# Sheet1.net
KiCad netlist of a schematic drawn in Altium Designer
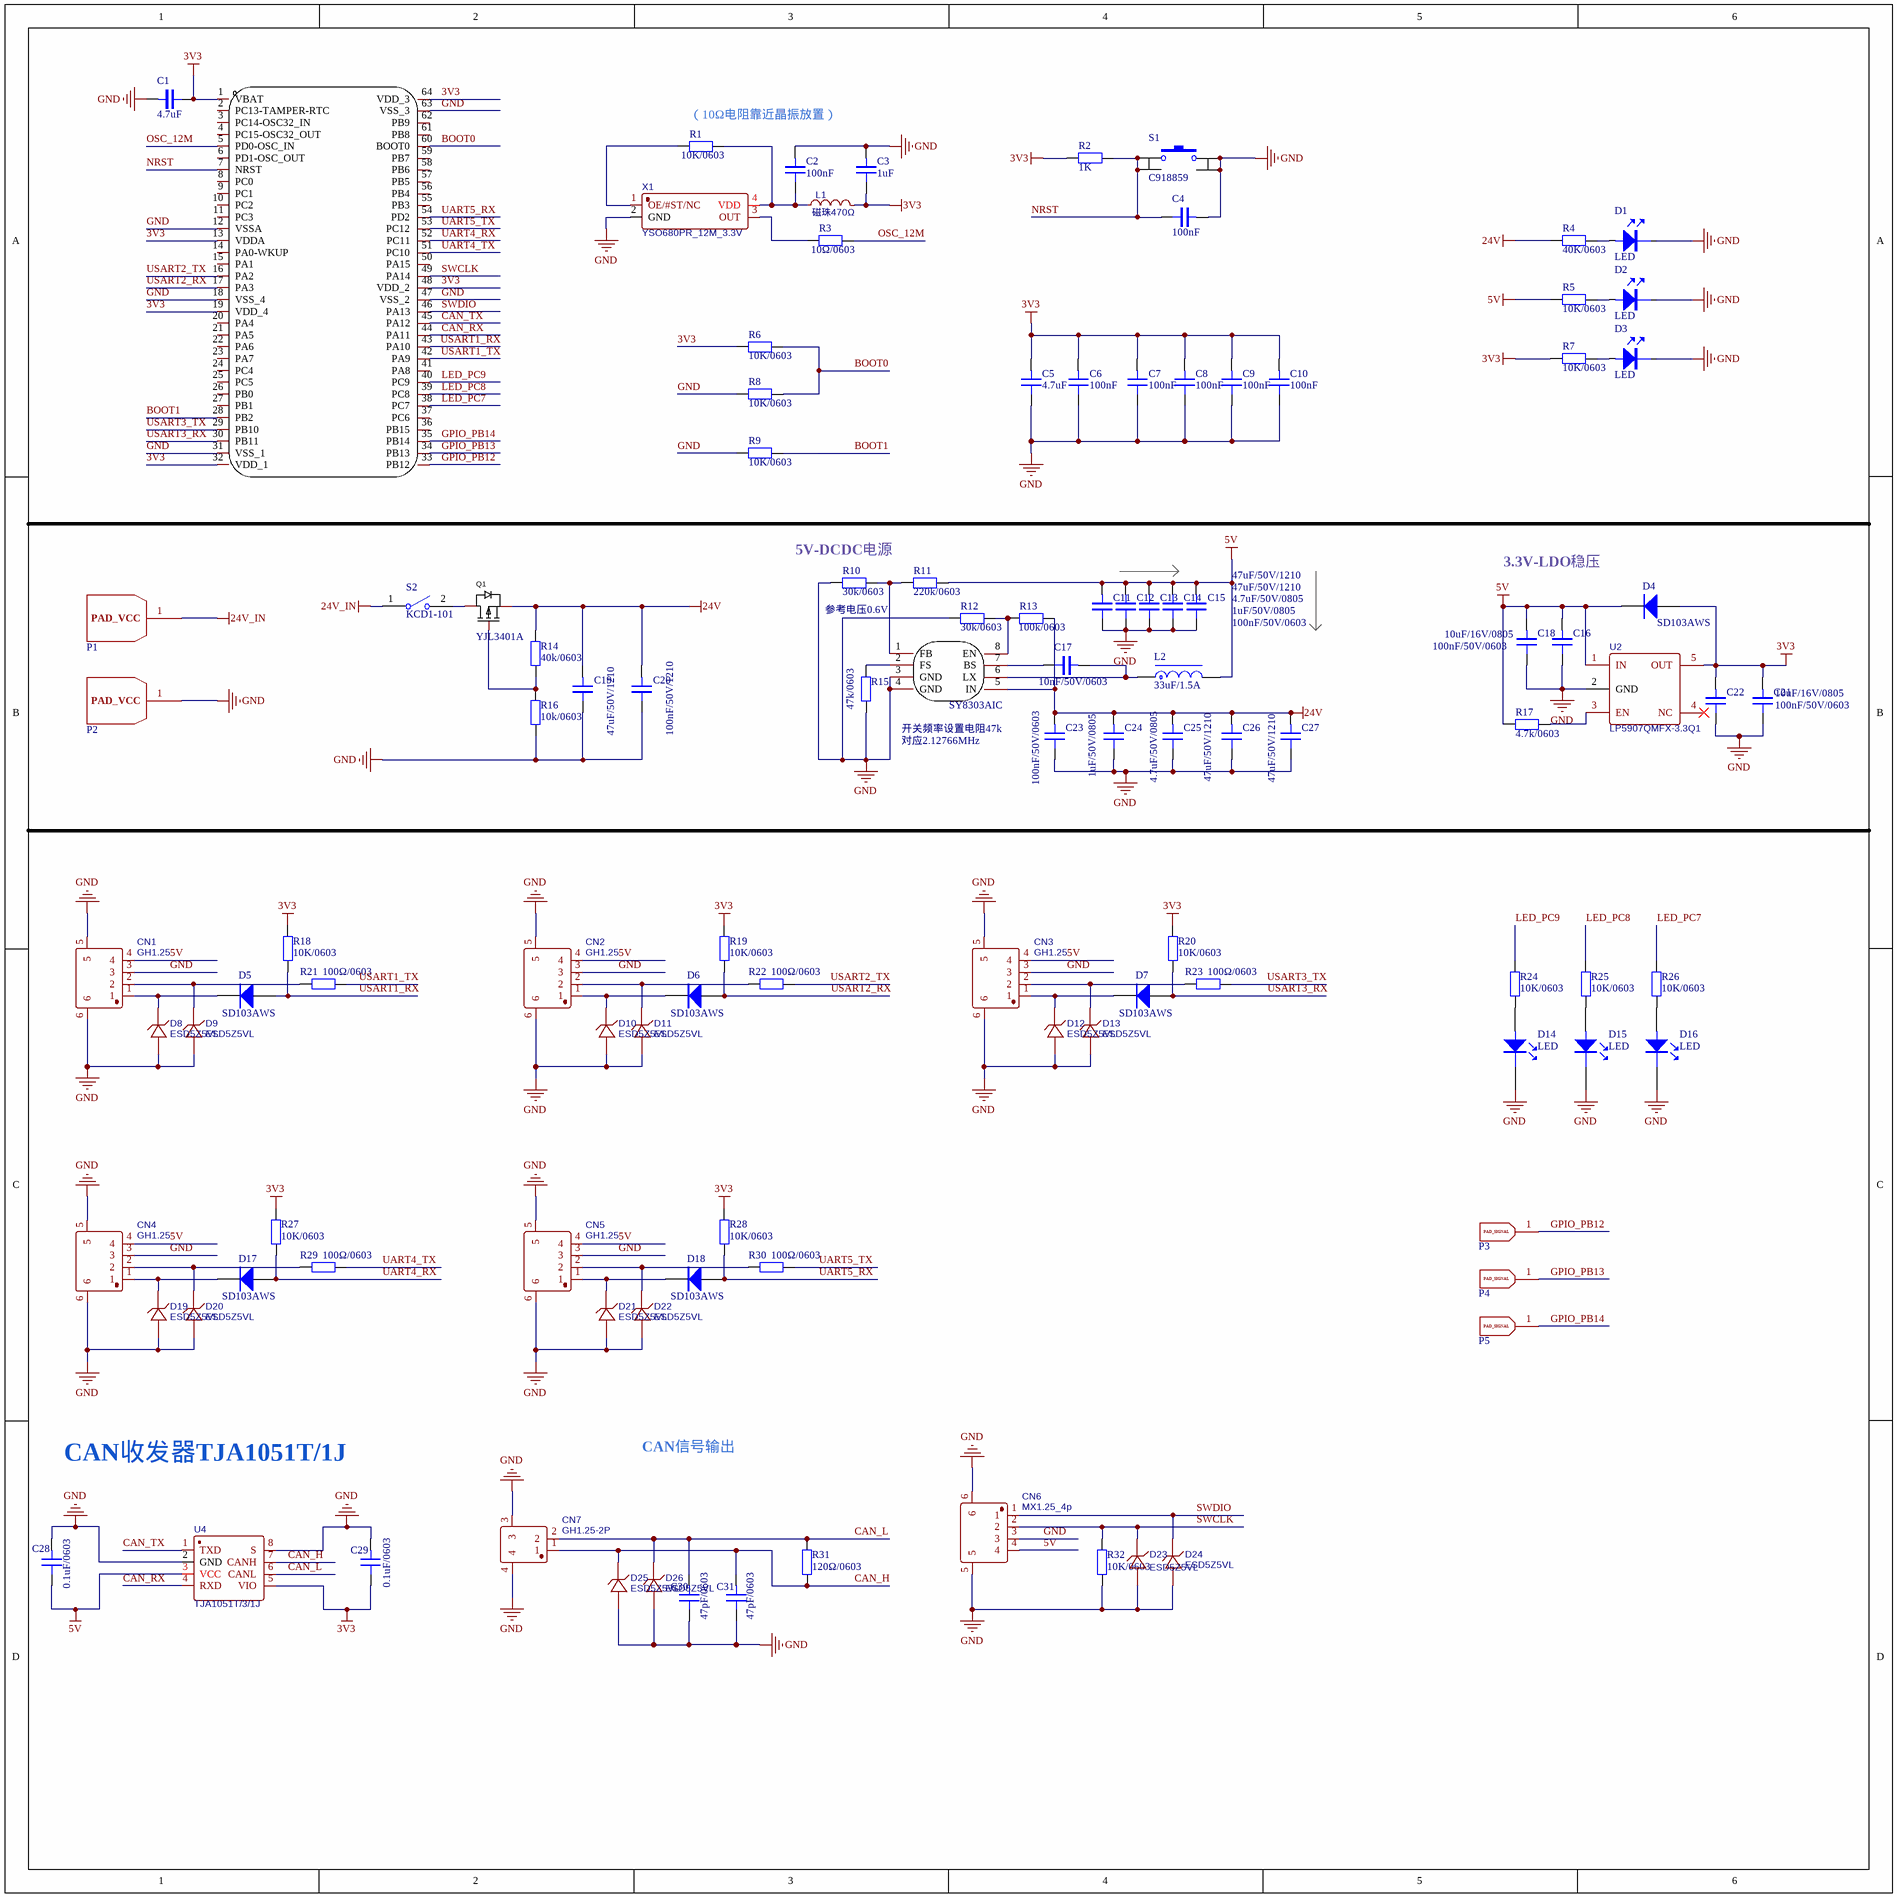
[diagram p0: Sheet1.SchDoc]

(export (version "E")
  (design (tool "Eeschema 10.0.6"))
  (components
    (comp (ref "C1")
      (value "4.7uF")
      (footprint "C 0603_L")
      (description "陶瓷电容")
      (libsource (lib "HERO_通用") (part "CAP"))
    )
    (comp (ref "C2")
      (value "100nF")
      (footprint "C 0603_L")
      (description "陶瓷电容")
      (libsource (lib "HERO_通用") (part "CAP"))
    )
    (comp (ref "C3")
      (value "1uF")
      (footprint "C 0603_L")
      (description "陶瓷电容")
      (libsource (lib "HERO_通用") (part "CAP"))
    )
    (comp (ref "C4")
      (value "100nF")
      (footprint "C 0603_L")
      (description "陶瓷电容")
      (libsource (lib "HERO_通用") (part "CAP"))
    )
    (comp (ref "C5")
      (value "4.7uF")
      (footprint "C 0603_L")
      (description "陶瓷电容")
      (libsource (lib "HERO_通用") (part "CAP"))
    )
    (comp (ref "C6")
      (value "100nF")
      (footprint "C 0603_L")
      (description "陶瓷电容")
      (libsource (lib "HERO_通用") (part "CAP"))
    )
    (comp (ref "C7")
      (value "100nF")
      (footprint "C 0603_L")
      (description "陶瓷电容")
      (libsource (lib "HERO_通用") (part "CAP"))
    )
    (comp (ref "C8")
      (value "100nF")
      (footprint "C 0603_L")
      (description "陶瓷电容")
      (libsource (lib "HERO_通用") (part "CAP"))
    )
    (comp (ref "C9")
      (value "100nF")
      (footprint "C 0603_L")
      (description "陶瓷电容")
      (libsource (lib "HERO_通用") (part "CAP"))
    )
    (comp (ref "C10")
      (value "100nF")
      (footprint "C 0603_L")
      (description "陶瓷电容")
      (libsource (lib "HERO_通用") (part "CAP"))
    )
    (comp (ref "C11")
      (value "47uF/50V/1210")
      (footprint "C 1210_L")
      (description "陶瓷电容")
      (libsource (lib "HERO_通用") (part "CAP"))
    )
    (comp (ref "C12")
      (value "47uF/50V/1210")
      (footprint "C 1210_L")
      (description "陶瓷电容")
      (libsource (lib "HERO_通用") (part "CAP"))
    )
    (comp (ref "C13")
      (value "4.7uF/50V/0805")
      (footprint "C 0805_L")
      (description "陶瓷电容")
      (libsource (lib "HERO_通用") (part "CAP"))
    )
    (comp (ref "C14")
      (value "1uF/50V/0805")
      (footprint "C 0805_L")
      (description "陶瓷电容")
      (libsource (lib "HERO_通用") (part "CAP"))
    )
    (comp (ref "C15")
      (value "100nF/50V/0603")
      (footprint "C 0603_L")
      (description "陶瓷电容")
      (libsource (lib "HERO_通用") (part "CAP"))
    )
    (comp (ref "C16")
      (value "100nF/50V/0603")
      (footprint "C 0603_L")
      (description "Capacitor")
      (libsource (lib "DJI_Armer") (part "CAP"))
    )
    (comp (ref "C17")
      (value "10nF/50V/0603")
      (footprint "C 0603_L")
      (description "陶瓷电容")
      (libsource (lib "HERO_通用") (part "CAP"))
    )
    (comp (ref "C18")
      (value "10uF/16V/0805")
      (footprint "C 0805_L")
      (description "陶瓷电容")
      (libsource (lib "HERO_通用") (part "CAP"))
    )
    (comp (ref "C19")
      (value "47uF/50V/1210")
      (footprint "C 1210_L")
      (description "陶瓷电容")
      (libsource (lib "HERO_通用") (part "CAP"))
    )
    (comp (ref "C20")
      (value "100nF/50V/1210")
      (footprint "C 0603_L")
      (description "陶瓷电容")
      (libsource (lib "HERO_通用") (part "CAP"))
    )
    (comp (ref "C21")
      (value "100nF/50V/0603")
      (footprint "C 0603_L")
      (description "Capacitor")
      (libsource (lib "DJI_Armer") (part "CAP"))
    )
    (comp (ref "C22")
      (value "10uF/16V/0805")
      (footprint "C 0805_L")
      (description "陶瓷电容")
      (libsource (lib "HERO_通用") (part "CAP"))
    )
    (comp (ref "C23")
      (value "100nF/50V/0603")
      (footprint "C 0603_L")
      (description "陶瓷电容")
      (libsource (lib "HERO_通用") (part "CAP"))
    )
    (comp (ref "C24")
      (value "1uF/50V/0805")
      (footprint "C 0805_L")
      (description "陶瓷电容")
      (libsource (lib "HERO_通用") (part "CAP"))
    )
    (comp (ref "C25")
      (value "4.7uF/50V/0805")
      (footprint "C 0805_L")
      (description "陶瓷电容")
      (libsource (lib "HERO_通用") (part "CAP"))
    )
    (comp (ref "C26")
      (value "47uF/50V/1210")
      (footprint "C 1210_L")
      (description "陶瓷电容")
      (libsource (lib "HERO_通用") (part "CAP"))
    )
    (comp (ref "C27")
      (value "47uF/50V/1210")
      (footprint "C 1210_L")
      (description "陶瓷电容")
      (libsource (lib "HERO_通用") (part "CAP"))
    )
    (comp (ref "C28")
      (value "0.1uF/0603")
      (footprint "C 0603_L")
      (description "陶瓷电容")
      (libsource (lib "HERO_通用") (part "CAP"))
    )
    (comp (ref "C29")
      (value "0.1uF/0603")
      (footprint "C 0603_L")
      (description "陶瓷电容")
      (libsource (lib "HERO_通用") (part "CAP"))
    )
    (comp (ref "C30")
      (value "47pF/0603")
      (footprint "C 0603_L")
      (description "陶瓷电容")
      (libsource (lib "HERO_通用") (part "CAP"))
    )
    (comp (ref "C31")
      (value "47pF/0603")
      (footprint "C 0603_L")
      (description "陶瓷电容")
      (libsource (lib "HERO_通用") (part "CAP"))
    )
    (comp (ref "CN1")
      (value "GH1.25")
      (footprint "GH1.25 4P-WT")
      (description "连接端子")
      (fields
        (field (name "BOM_SUPPLIER PART") "C225127")
        (field (name "BOM_MANUFACTURER PART") "A1257WR-S-4P")
        (field (name "CONTRIBUTOR") "LCSC")
      )
      (libsource (lib "HERO_交互") (part "GH1.25 4p"))
    )
    (comp (ref "CN2")
      (value "GH1.25")
      (footprint "GH1.25 4P-WT")
      (description "连接端子")
      (fields
        (field (name "BOM_SUPPLIER PART") "C225127")
        (field (name "BOM_MANUFACTURER PART") "A1257WR-S-4P")
        (field (name "CONTRIBUTOR") "LCSC")
      )
      (libsource (lib "HERO_交互") (part "GH1.25 4p"))
    )
    (comp (ref "CN3")
      (value "GH1.25")
      (footprint "GH1.25 4P-WT")
      (description "连接端子")
      (fields
        (field (name "BOM_SUPPLIER PART") "C225127")
        (field (name "BOM_MANUFACTURER PART") "A1257WR-S-4P")
        (field (name "CONTRIBUTOR") "LCSC")
      )
      (libsource (lib "HERO_交互") (part "GH1.25 4p"))
    )
    (comp (ref "CN4")
      (value "GH1.25")
      (footprint "GH1.25 4P-WT")
      (description "连接端子")
      (fields
        (field (name "BOM_SUPPLIER PART") "C225127")
        (field (name "BOM_MANUFACTURER PART") "A1257WR-S-4P")
        (field (name "CONTRIBUTOR") "LCSC")
      )
      (libsource (lib "HERO_交互") (part "GH1.25 4p"))
    )
    (comp (ref "CN5")
      (value "GH1.25")
      (footprint "GH1.25 4P-WT")
      (description "连接端子")
      (fields
        (field (name "BOM_SUPPLIER PART") "C225127")
        (field (name "BOM_MANUFACTURER PART") "A1257WR-S-4P")
        (field (name "CONTRIBUTOR") "LCSC")
      )
      (libsource (lib "HERO_交互") (part "GH1.25 4p"))
    )
    (comp (ref "CN6")
      (value "MX1.25_4p")
      (footprint "MX1.25_4PIN")
      (description "连接端子")
      (fields
        (field (name "BOM_SUPPLIER PART") "C225127")
        (field (name "BOM_MANUFACTURER PART") "A1257WR-S-4P")
        (field (name "CONTRIBUTOR") "LCSC")
      )
      (libsource (lib "HERO_交互") (part "MX1.25_4p"))
    )
    (comp (ref "CN7")
      (value "GH1.25-2P")
      (footprint "GH1.25-2P-LT")
      (description "连接端子")
      (fields
        (field (name "BOM_SUPPLIER PART") "C225125")
        (field (name "BOM_MANUFACTURER PART") "A1257WR-S-2P")
        (field (name "CONTRIBUTOR") "LCSC")
      )
      (libsource (lib "HERO_交互") (part "GH1.25-2P"))
    )
    (comp (ref "D1")
      (value "LED")
      (footprint "LED_0603")
      (description "发光二极管")
      (libsource (lib "HERO_通用") (part "LED"))
    )
    (comp (ref "D2")
      (value "LED")
      (footprint "LED_0603")
      (description "发光二极管")
      (libsource (lib "HERO_通用") (part "LED"))
    )
    (comp (ref "D3")
      (value "LED")
      (footprint "LED_0603")
      (description "发光二极管")
      (libsource (lib "HERO_通用") (part "LED"))
    )
    (comp (ref "D4")
      (value "SD103AWS")
      (footprint "SOD-323")
      (description "二极管")
      (libsource (lib "DJI_Armer") (part "SD103AWS"))
    )
    (comp (ref "D5")
      (value "SD103AWS")
      (footprint "SOD-323")
      (description "二极管")
      (libsource (lib "DJI_Armer") (part "SD103AWS"))
    )
    (comp (ref "D6")
      (value "SD103AWS")
      (footprint "SOD-323")
      (description "二极管")
      (libsource (lib "DJI_Armer") (part "SD103AWS"))
    )
    (comp (ref "D7")
      (value "SD103AWS")
      (footprint "SOD-323")
      (description "二极管")
      (libsource (lib "DJI_Armer") (part "SD103AWS"))
    )
    (comp (ref "D8")
      (value "ESD5Z5VL")
      (footprint "SOD-523")
      (description "ESD 单向 5V")
      (fields
        (field (name "BOM_MANUFACTURER PART") "SMF6.5A")
        (field (name "BOM_SUPPLIER PART") "C123792")
        (field (name "CONTRIBUTOR") "LCSC")
      )
      (libsource (lib "HERO_通用") (part "ESD5Z5VL"))
    )
    (comp (ref "D9")
      (value "ESD5Z5VL")
      (footprint "SOD-523")
      (description "ESD 单向 5V")
      (fields
        (field (name "BOM_MANUFACTURER PART") "SMF6.5A")
        (field (name "BOM_SUPPLIER PART") "C123792")
        (field (name "CONTRIBUTOR") "LCSC")
      )
      (libsource (lib "HERO_通用") (part "ESD5Z5VL"))
    )
    (comp (ref "D10")
      (value "ESD5Z5VL")
      (footprint "SOD-523")
      (description "ESD 单向 5V")
      (fields
        (field (name "BOM_MANUFACTURER PART") "SMF6.5A")
        (field (name "BOM_SUPPLIER PART") "C123792")
        (field (name "CONTRIBUTOR") "LCSC")
      )
      (libsource (lib "HERO_通用") (part "ESD5Z5VL"))
    )
    (comp (ref "D11")
      (value "ESD5Z5VL")
      (footprint "SOD-523")
      (description "ESD 单向 5V")
      (fields
        (field (name "BOM_MANUFACTURER PART") "SMF6.5A")
        (field (name "BOM_SUPPLIER PART") "C123792")
        (field (name "CONTRIBUTOR") "LCSC")
      )
      (libsource (lib "HERO_通用") (part "ESD5Z5VL"))
    )
    (comp (ref "D12")
      (value "ESD5Z5VL")
      (footprint "SOD-523")
      (description "ESD 单向 5V")
      (fields
        (field (name "BOM_MANUFACTURER PART") "SMF6.5A")
        (field (name "BOM_SUPPLIER PART") "C123792")
        (field (name "CONTRIBUTOR") "LCSC")
      )
      (libsource (lib "HERO_通用") (part "ESD5Z5VL"))
    )
    (comp (ref "D13")
      (value "ESD5Z5VL")
      (footprint "SOD-523")
      (description "ESD 单向 5V")
      (fields
        (field (name "BOM_MANUFACTURER PART") "SMF6.5A")
        (field (name "BOM_SUPPLIER PART") "C123792")
        (field (name "CONTRIBUTOR") "LCSC")
      )
      (libsource (lib "HERO_通用") (part "ESD5Z5VL"))
    )
    (comp (ref "D14")
      (value "LED")
      (footprint "LED_0603")
      (description "发光二极管")
      (libsource (lib "") (part "LED_1"))
    )
    (comp (ref "D15")
      (value "LED")
      (footprint "LED_0603")
      (description "发光二极管")
      (libsource (lib "") (part "LED_1"))
    )
    (comp (ref "D16")
      (value "LED")
      (footprint "LED_0603")
      (description "发光二极管")
      (libsource (lib "") (part "LED_1"))
    )
    (comp (ref "D17")
      (value "SD103AWS")
      (footprint "SOD-323")
      (description "二极管")
      (libsource (lib "DJI_Armer") (part "SD103AWS"))
    )
    (comp (ref "D18")
      (value "SD103AWS")
      (footprint "SOD-323")
      (description "二极管")
      (libsource (lib "DJI_Armer") (part "SD103AWS"))
    )
    (comp (ref "D19")
      (value "ESD5Z5VL")
      (footprint "SOD-523")
      (description "ESD 单向 5V")
      (fields
        (field (name "BOM_MANUFACTURER PART") "SMF6.5A")
        (field (name "BOM_SUPPLIER PART") "C123792")
        (field (name "CONTRIBUTOR") "LCSC")
      )
      (libsource (lib "HERO_通用") (part "ESD5Z5VL"))
    )
    (comp (ref "D20")
      (value "ESD5Z5VL")
      (footprint "SOD-523")
      (description "ESD 单向 5V")
      (fields
        (field (name "BOM_MANUFACTURER PART") "SMF6.5A")
        (field (name "BOM_SUPPLIER PART") "C123792")
        (field (name "CONTRIBUTOR") "LCSC")
      )
      (libsource (lib "HERO_通用") (part "ESD5Z5VL"))
    )
    (comp (ref "D21")
      (value "ESD5Z5VL")
      (footprint "SOD-523")
      (description "ESD 单向 5V")
      (fields
        (field (name "BOM_MANUFACTURER PART") "SMF6.5A")
        (field (name "BOM_SUPPLIER PART") "C123792")
        (field (name "CONTRIBUTOR") "LCSC")
      )
      (libsource (lib "HERO_通用") (part "ESD5Z5VL"))
    )
    (comp (ref "D22")
      (value "ESD5Z5VL")
      (footprint "SOD-523")
      (description "ESD 单向 5V")
      (fields
        (field (name "BOM_MANUFACTURER PART") "SMF6.5A")
        (field (name "BOM_SUPPLIER PART") "C123792")
        (field (name "CONTRIBUTOR") "LCSC")
      )
      (libsource (lib "HERO_通用") (part "ESD5Z5VL"))
    )
    (comp (ref "D23")
      (value "ESD5Z5VL")
      (footprint "SOD-523")
      (description "ESD 单向 5V")
      (fields
        (field (name "BOM_MANUFACTURER PART") "SMF6.5A")
        (field (name "BOM_SUPPLIER PART") "C123792")
        (field (name "CONTRIBUTOR") "LCSC")
      )
      (libsource (lib "HERO_通用") (part "ESD5Z5VL"))
    )
    (comp (ref "D24")
      (value "ESD5Z5VL")
      (footprint "SOD-523")
      (description "ESD 单向 5V")
      (fields
        (field (name "BOM_MANUFACTURER PART") "SMF6.5A")
        (field (name "BOM_SUPPLIER PART") "C123792")
        (field (name "CONTRIBUTOR") "LCSC")
      )
      (libsource (lib "HERO_通用") (part "ESD5Z5VL"))
    )
    (comp (ref "D25")
      (value "ESD5Z5VL")
      (footprint "SOD-523")
      (description "ESD 单向 5V")
      (fields
        (field (name "BOM_MANUFACTURER PART") "SMF6.5A")
        (field (name "BOM_SUPPLIER PART") "C123792")
        (field (name "CONTRIBUTOR") "LCSC")
      )
      (libsource (lib "HERO_通用") (part "ESD5Z5VL"))
    )
    (comp (ref "D26")
      (value "ESD5Z5VL")
      (footprint "SOD-523")
      (description "ESD 单向 5V")
      (fields
        (field (name "BOM_MANUFACTURER PART") "SMF6.5A")
        (field (name "BOM_SUPPLIER PART") "C123792")
        (field (name "CONTRIBUTOR") "LCSC")
      )
      (libsource (lib "HERO_通用") (part "ESD5Z5VL"))
    )
    (comp (ref "L1")
      (value "磁珠470Ω")
      (footprint "C 0603_L")
      (fields
        (field (name "BOM_MANUFACTURER PART") "UPZ1608U471-1R5TF")
        (field (name "BOM_SUPPLIER PART") "C74335")
      )
      (libsource (lib "HERO_通用") (part "磁珠470Ω"))
    )
    (comp (ref "L2")
      (value "33uF/1.5A")
      (footprint "IND-SMD_L7.3-W7.3")
      (description "贴片功率电感")
      (libsource (lib "Schlib1") (part "L-SMD"))
    )
    (comp (ref "P1") (value "PAD_VCC") (footprint "PAD_VCC") (libsource (lib "HERO_模块") (part "PAD_VCC")))
    (comp (ref "P2") (value "PAD_VCC") (footprint "PAD_VCC") (libsource (lib "HERO_模块") (part "PAD_VCC")))
    (comp (ref "P3")
      (value "PAD_Signal")
      (footprint "pad_signal")
      (libsource (lib "HERO_模块") (part "PAD_Signal"))
    )
    (comp (ref "P4")
      (value "PAD_Signal")
      (footprint "pad_signal")
      (libsource (lib "HERO_模块") (part "PAD_Signal"))
    )
    (comp (ref "P5")
      (value "PAD_Signal")
      (footprint "pad_signal")
      (libsource (lib "HERO_模块") (part "PAD_Signal"))
    )
    (comp (ref "Q1")
      (value "YJL3401A")
      (footprint "SOT-23-3_L2.9-W1.3-P1.90-LS2.4-BR")
      (fields (field (name "MANUFACTURER") "YANGJIE(扬杰)"))
      (libsource (lib "EG_slave_STCG12") (part "YJL3401A"))
    )
    (comp (ref "R1")
      (value "10K/0603")
      (footprint "R 0603_S")
      (description "贴片电阻")
      (libsource (lib "HERO_通用") (part "RES"))
    )
    (comp (ref "R2")
      (value "1K")
      (footprint "R 0603_S")
      (description "贴片电阻")
      (libsource (lib "HERO_通用") (part "RES"))
    )
    (comp (ref "R3")
      (value "10Ω/0603")
      (footprint "R 0603_S")
      (description "贴片电阻")
      (libsource (lib "HERO_通用") (part "RES"))
    )
    (comp (ref "R4")
      (value "40K/0603")
      (footprint "R 0603_S")
      (description "贴片电阻")
      (libsource (lib "HERO_通用") (part "RES"))
    )
    (comp (ref "R5")
      (value "10K/0603")
      (footprint "R 0603_S")
      (description "贴片电阻")
      (libsource (lib "HERO_通用") (part "RES"))
    )
    (comp (ref "R6")
      (value "10K/0603")
      (footprint "R 0603_S")
      (description "贴片电阻")
      (libsource (lib "HERO_通用") (part "RES"))
    )
    (comp (ref "R7")
      (value "10K/0603")
      (footprint "R 0603_S")
      (description "贴片电阻")
      (libsource (lib "HERO_通用") (part "RES"))
    )
    (comp (ref "R8")
      (value "10K/0603")
      (footprint "R 0603_S")
      (description "贴片电阻")
      (libsource (lib "HERO_通用") (part "RES"))
    )
    (comp (ref "R9")
      (value "10K/0603")
      (footprint "R 0603_S")
      (description "贴片电阻")
      (libsource (lib "HERO_通用") (part "RES"))
    )
    (comp (ref "R10")
      (value "30k/0603")
      (footprint "R 0603_S")
      (description "贴片电阻")
      (libsource (lib "HERO_通用") (part "RES"))
    )
    (comp (ref "R11")
      (value "220k/0603")
      (footprint "R 0603_S")
      (description "贴片电阻")
      (libsource (lib "HERO_通用") (part "RES"))
    )
    (comp (ref "R12")
      (value "30k/0603")
      (footprint "R 0603_S")
      (description "贴片电阻")
      (libsource (lib "HERO_通用") (part "RES"))
    )
    (comp (ref "R13")
      (value "100k/0603")
      (footprint "R 0603_S")
      (description "贴片电阻")
      (libsource (lib "HERO_通用") (part "RES"))
    )
    (comp (ref "R14")
      (value "40k/0603")
      (footprint "R 0603_S")
      (description "贴片电阻")
      (libsource (lib "") (part "RES_1"))
    )
    (comp (ref "R15")
      (value "47k/0603")
      (footprint "R 0603_S")
      (description "贴片电阻")
      (libsource (lib "") (part "RES_1"))
    )
    (comp (ref "R16")
      (value "10k/0603")
      (footprint "R 0603_S")
      (description "贴片电阻")
      (libsource (lib "") (part "RES_1"))
    )
    (comp (ref "R17")
      (value "4.7k/0603")
      (footprint "R 0603_S")
      (description "贴片电阻")
      (libsource (lib "HERO_通用") (part "RES"))
    )
    (comp (ref "R18")
      (value "10K/0603")
      (footprint "R 0603_S")
      (description "贴片电阻")
      (libsource (lib "") (part "RES_1"))
    )
    (comp (ref "R19")
      (value "10K/0603")
      (footprint "R 0603_S")
      (description "贴片电阻")
      (libsource (lib "") (part "RES_1"))
    )
    (comp (ref "R20")
      (value "10K/0603")
      (footprint "R 0603_S")
      (description "贴片电阻")
      (libsource (lib "") (part "RES_1"))
    )
    (comp (ref "R21")
      (value "100Ω/0603")
      (footprint "R 0603_S")
      (description "贴片电阻")
      (libsource (lib "HERO_通用") (part "RES"))
    )
    (comp (ref "R22")
      (value "100Ω/0603")
      (footprint "R 0603_S")
      (description "贴片电阻")
      (libsource (lib "HERO_通用") (part "RES"))
    )
    (comp (ref "R23")
      (value "100Ω/0603")
      (footprint "R 0603_S")
      (description "贴片电阻")
      (libsource (lib "HERO_通用") (part "RES"))
    )
    (comp (ref "R24")
      (value "10K/0603")
      (footprint "R 0603_S")
      (description "贴片电阻")
      (libsource (lib "") (part "RES_1"))
    )
    (comp (ref "R25")
      (value "10K/0603")
      (footprint "R 0603_S")
      (description "贴片电阻")
      (libsource (lib "") (part "RES_1"))
    )
    (comp (ref "R26")
      (value "10K/0603")
      (footprint "R 0603_S")
      (description "贴片电阻")
      (libsource (lib "") (part "RES_1"))
    )
    (comp (ref "R27")
      (value "10K/0603")
      (footprint "R 0603_S")
      (description "贴片电阻")
      (libsource (lib "") (part "RES_1"))
    )
    (comp (ref "R28")
      (value "10K/0603")
      (footprint "R 0603_S")
      (description "贴片电阻")
      (libsource (lib "") (part "RES_1"))
    )
    (comp (ref "R29")
      (value "100Ω/0603")
      (footprint "R 0603_S")
      (description "贴片电阻")
      (libsource (lib "HERO_通用") (part "RES"))
    )
    (comp (ref "R30")
      (value "100Ω/0603")
      (footprint "R 0603_S")
      (description "贴片电阻")
      (libsource (lib "HERO_通用") (part "RES"))
    )
    (comp (ref "R31")
      (value "120Ω/0603")
      (footprint "R 0603_S")
      (description "贴片电阻")
      (libsource (lib "") (part "RES_1"))
    )
    (comp (ref "R32")
      (value "10K/0603")
      (footprint "R 0603_S")
      (description "贴片电阻")
      (libsource (lib "") (part "RES_1"))
    )
    (comp (ref "S1")
      (value "C918859")
      (footprint "KEY-4.2*3.25")
      (description "DJI御用小按键")
      (libsource (lib "HERO_交互") (part "按键"))
    )
    (comp (ref "S2")
      (value "KCD1-101")
      (footprint "SW-TH_MR5-111-C5N-BB")
      (description "单刀单掷 直插立式")
      (libsource (lib "HERO_交互") (part "KCD1-101"))
    )
    (comp (ref "U1")
      (value "STM32F103RCT6")
      (footprint "LQFP-64_L10.0-W10.0-P0.50-LS12.0-BL")
      (fields (field (name "MANUFACTURER") "ST(意法半导体)"))
      (libsource (lib "Schlib1") (part "STM32F103RCT6"))
    )
    (comp (ref "U2")
      (value "LP5907QMFX-3.3Q1")
      (footprint "SOT23-5N")
      (fields (field (name "BOM_SUPPLIER PART") "C130005") (field (name "CONTRIBUTOR") "LCSC"))
      (libsource (lib "DJI_Armer") (part "LP5907QMFX-3.3Q1"))
    )
    (comp (ref "U3")
      (value "SY8303AIC")
      (footprint "TSOT-23-8_L2.9-W1.6-P0.65-LS2.8-BR")
      (description "DCDC ADJ 3A")
      (fields (field (name "MANUFACTURER") "矽力杰silergy"))
      (libsource (lib "HERO_IC") (part "SY8303AIC"))
    )
    (comp (ref "U4")
      (value "TJA1051T/3/1J")
      (footprint "SOP8_L")
      (description "CAN芯片")
      (fields (field (name "BOM_SUPPLIER PART") "C38695"))
      (libsource (lib "HERO_IC") (part "TJA1051T/3/1J"))
    )
    (comp (ref "X1")
      (value "YSO680PR_12M_3.3V")
      (footprint "OSC 3225-4P")
      (description "有源晶振12M")
      (fields
        (field (name "BOM_SUPPLIER PART") "C382483")
        (field (name "BOM_MANUFACTURER PART") "OP322512MEDA4SI-u")
        (field (name "CONTRIBUTOR") "LCSC")
      )
      (libsource (lib "HERO_IC") (part "YSO680PR_12M_3.3V"))
    )
  )
  (nets
    (net (code "1") (name "/BOOT0") (class "Default")
      (node (ref "R6") (pin "2") (pinfunction "2_2") (pintype "passive"))
      (node (ref "R8") (pin "2") (pinfunction "2_2") (pintype "passive"))
      (node (ref "U1") (pin "60") (pinfunction "BOOT0_60") (pintype "passive"))
    )
    (net (code "2") (name "/BOOT1") (class "Default")
      (node (ref "R9") (pin "2") (pinfunction "2_2") (pintype "passive"))
      (node (ref "U1") (pin "28") (pinfunction "PB2_28") (pintype "passive"))
    )
    (net (code "3") (name "/CAN_H") (class "Default")
      (node (ref "C31") (pin "1") (pinfunction "1_1") (pintype "passive"))
      (node (ref "CN7") (pin "1") (pinfunction "1_1") (pintype "passive"))
      (node (ref "D25") (pin "2") (pinfunction "C_2") (pintype "passive"))
      (node (ref "R31") (pin "2") (pinfunction "2_2") (pintype "passive"))
      (node (ref "U4") (pin "7") (pinfunction "CANH_7") (pintype "passive"))
    )
    (net (code "4") (name "/CAN_L") (class "Default")
      (node (ref "C30") (pin "1") (pinfunction "1_1") (pintype "passive"))
      (node (ref "CN7") (pin "2") (pinfunction "2_2") (pintype "passive"))
      (node (ref "D26") (pin "2") (pinfunction "C_2") (pintype "passive"))
      (node (ref "R31") (pin "1") (pinfunction "1_1") (pintype "passive"))
      (node (ref "U4") (pin "6") (pinfunction "CANL_6") (pintype "passive"))
    )
    (net (code "5") (name "/CAN_RX") (class "Default")
      (node (ref "U1") (pin "44") (pinfunction "PA11_44") (pintype "passive"))
      (node (ref "U4") (pin "4") (pinfunction "RXD_4") (pintype "passive"))
    )
    (net (code "6") (name "/CAN_TX") (class "Default")
      (node (ref "U1") (pin "45") (pinfunction "PA12_45") (pintype "passive"))
      (node (ref "U4") (pin "1") (pinfunction "TXD_1") (pintype "passive"))
    )
    (net (code "7") (name "/GPIO_PB12") (class "Default")
      (node (ref "P3") (pin "1") (pinfunction "PAD_SIGNAL_1") (pintype "passive"))
      (node (ref "U1") (pin "33") (pinfunction "PB12_33") (pintype "passive"))
    )
    (net (code "8") (name "/GPIO_PB13") (class "Default")
      (node (ref "P4") (pin "1") (pinfunction "PAD_SIGNAL_1") (pintype "passive"))
      (node (ref "U1") (pin "34") (pinfunction "PB13_34") (pintype "passive"))
    )
    (net (code "9") (name "/GPIO_PB14") (class "Default")
      (node (ref "P5") (pin "1") (pinfunction "PAD_SIGNAL_1") (pintype "passive"))
      (node (ref "U1") (pin "35") (pinfunction "PB14_35") (pintype "passive"))
    )
    (net (code "10") (name "/LED_PC7") (class "Default")
      (node (ref "R26") (pin "1") (pinfunction "1_1") (pintype "passive"))
      (node (ref "U1") (pin "38") (pinfunction "PC7_38") (pintype "passive"))
    )
    (net (code "11") (name "/LED_PC8") (class "Default")
      (node (ref "R25") (pin "1") (pinfunction "1_1") (pintype "passive"))
      (node (ref "U1") (pin "39") (pinfunction "PC8_39") (pintype "passive"))
    )
    (net (code "12") (name "/LED_PC9") (class "Default")
      (node (ref "R24") (pin "1") (pinfunction "1_1") (pintype "passive"))
      (node (ref "U1") (pin "40") (pinfunction "PC9_40") (pintype "passive"))
    )
    (net (code "13") (name "/NRST") (class "Default")
      (node (ref "C4") (pin "2") (pinfunction "2_2") (pintype "passive"))
      (node (ref "R2") (pin "2") (pinfunction "2_2") (pintype "passive"))
      (node (ref "S1") (pin "1") (pinfunction "1_1") (pintype "passive"))
      (node (ref "S1") (pin "2") (pinfunction "2_2") (pintype "passive"))
      (node (ref "U1") (pin "7") (pinfunction "NRST_7") (pintype "passive"))
    )
    (net (code "14") (name "/OSC_12M") (class "Default")
      (node (ref "R3") (pin "2") (pinfunction "2_2") (pintype "passive"))
      (node (ref "U1") (pin "5") (pinfunction "PD0-OSC_IN_5") (pintype "passive"))
    )
    (net (code "15") (name "/SWCLK") (class "Default")
      (node (ref "CN6") (pin "2") (pinfunction "2_2") (pintype "passive"))
      (node (ref "D23") (pin "2") (pinfunction "C_2") (pintype "passive"))
      (node (ref "R32") (pin "1") (pinfunction "1_1") (pintype "passive"))
      (node (ref "U1") (pin "49") (pinfunction "PA14_49") (pintype "passive"))
    )
    (net (code "16") (name "/SWDIO") (class "Default")
      (node (ref "CN6") (pin "1") (pinfunction "1_1") (pintype "passive"))
      (node (ref "D24") (pin "2") (pinfunction "C_2") (pintype "passive"))
      (node (ref "U1") (pin "46") (pinfunction "PA13_46") (pintype "passive"))
    )
    (net (code "17") (name "/UART4_RX") (class "Default")
      (node (ref "D17") (pin "1") (pinfunction "1_1") (pintype "passive"))
      (node (ref "R27") (pin "2") (pinfunction "2_2") (pintype "passive"))
      (node (ref "U1") (pin "52") (pinfunction "PC11_52") (pintype "passive"))
    )
    (net (code "18") (name "/UART4_TX") (class "Default")
      (node (ref "R29") (pin "2") (pinfunction "2_2") (pintype "passive"))
      (node (ref "U1") (pin "51") (pinfunction "PC10_51") (pintype "passive"))
    )
    (net (code "19") (name "/UART5_RX") (class "Default")
      (node (ref "D18") (pin "1") (pinfunction "1_1") (pintype "passive"))
      (node (ref "R28") (pin "2") (pinfunction "2_2") (pintype "passive"))
      (node (ref "U1") (pin "54") (pinfunction "PD2_54") (pintype "passive"))
    )
    (net (code "20") (name "/UART5_TX") (class "Default")
      (node (ref "R30") (pin "2") (pinfunction "2_2") (pintype "passive"))
      (node (ref "U1") (pin "53") (pinfunction "PC12_53") (pintype "passive"))
    )
    (net (code "21") (name "/USART1_RX") (class "Default")
      (node (ref "D5") (pin "1") (pinfunction "1_1") (pintype "passive"))
      (node (ref "R18") (pin "2") (pinfunction "2_2") (pintype "passive"))
      (node (ref "U1") (pin "43") (pinfunction "PA10_43") (pintype "passive"))
    )
    (net (code "22") (name "/USART1_TX") (class "Default")
      (node (ref "R21") (pin "2") (pinfunction "2_2") (pintype "passive"))
      (node (ref "U1") (pin "42") (pinfunction "PA9_42") (pintype "passive"))
    )
    (net (code "23") (name "/USART2_RX") (class "Default")
      (node (ref "D6") (pin "1") (pinfunction "1_1") (pintype "passive"))
      (node (ref "R19") (pin "2") (pinfunction "2_2") (pintype "passive"))
      (node (ref "U1") (pin "17") (pinfunction "PA3_17") (pintype "passive"))
    )
    (net (code "24") (name "/USART2_TX") (class "Default")
      (node (ref "R22") (pin "2") (pinfunction "2_2") (pintype "passive"))
      (node (ref "U1") (pin "16") (pinfunction "PA2_16") (pintype "passive"))
    )
    (net (code "25") (name "/USART3_RX") (class "Default")
      (node (ref "D7") (pin "1") (pinfunction "1_1") (pintype "passive"))
      (node (ref "R20") (pin "2") (pinfunction "2_2") (pintype "passive"))
      (node (ref "U1") (pin "30") (pinfunction "PB11_30") (pintype "passive"))
    )
    (net (code "26") (name "/USART3_TX") (class "Default")
      (node (ref "R23") (pin "2") (pinfunction "2_2") (pintype "passive"))
      (node (ref "U1") (pin "29") (pinfunction "PB10_29") (pintype "passive"))
    )
    (net (code "27") (name "3V3") (class "Default")
      (node (ref "C1") (pin "2") (pinfunction "2_2") (pintype "passive"))
      (node (ref "C10") (pin "1") (pinfunction "1_1") (pintype "passive"))
      (node (ref "C21") (pin "1") (pinfunction "1_1") (pintype "passive"))
      (node (ref "C22") (pin "1") (pinfunction "1_1") (pintype "passive"))
      (node (ref "C29") (pin "2") (pinfunction "2_2") (pintype "passive"))
      (node (ref "C3") (pin "2") (pinfunction "2_2") (pintype "passive"))
      (node (ref "C5") (pin "1") (pinfunction "1_1") (pintype "passive"))
      (node (ref "C6") (pin "1") (pinfunction "1_1") (pintype "passive"))
      (node (ref "C7") (pin "1") (pinfunction "1_1") (pintype "passive"))
      (node (ref "C8") (pin "1") (pinfunction "1_1") (pintype "passive"))
      (node (ref "C9") (pin "1") (pinfunction "1_1") (pintype "passive"))
      (node (ref "D4") (pin "1") (pinfunction "1_1") (pintype "passive"))
      (node (ref "L1") (pin "2") (pinfunction "2_2") (pintype "passive"))
      (node (ref "R18") (pin "1") (pinfunction "1_1") (pintype "passive"))
      (node (ref "R19") (pin "1") (pinfunction "1_1") (pintype "passive"))
      (node (ref "R2") (pin "1") (pinfunction "1_1") (pintype "passive"))
      (node (ref "R20") (pin "1") (pinfunction "1_1") (pintype "passive"))
      (node (ref "R27") (pin "1") (pinfunction "1_1") (pintype "passive"))
      (node (ref "R28") (pin "1") (pinfunction "1_1") (pintype "passive"))
      (node (ref "R6") (pin "1") (pinfunction "1_1") (pintype "passive"))
      (node (ref "R7") (pin "1") (pinfunction "1_1") (pintype "passive"))
      (node (ref "U1") (pin "1") (pinfunction "VBAT_1") (pintype "passive"))
      (node (ref "U1") (pin "13") (pinfunction "VDDA_13") (pintype "passive"))
      (node (ref "U1") (pin "19") (pinfunction "VDD_4_19") (pintype "passive"))
      (node (ref "U1") (pin "32") (pinfunction "VDD_1_32") (pintype "passive"))
      (node (ref "U1") (pin "48") (pinfunction "VDD_2_48") (pintype "passive"))
      (node (ref "U1") (pin "64") (pinfunction "VDD_3_64") (pintype "passive"))
      (node (ref "U2") (pin "5") (pinfunction "OUT_5") (pintype "passive"))
      (node (ref "U4") (pin "5") (pinfunction "VIO_5") (pintype "passive"))
    )
    (net (code "28") (name "5V") (class "Default")
      (node (ref "C11") (pin "1") (pinfunction "1_1") (pintype "passive"))
      (node (ref "C12") (pin "1") (pinfunction "1_1") (pintype "passive"))
      (node (ref "C13") (pin "1") (pinfunction "1_1") (pintype "passive"))
      (node (ref "C14") (pin "1") (pinfunction "1_1") (pintype "passive"))
      (node (ref "C15") (pin "1") (pinfunction "1_1") (pintype "passive"))
      (node (ref "C16") (pin "1") (pinfunction "1_1") (pintype "passive"))
      (node (ref "C18") (pin "1") (pinfunction "1_1") (pintype "passive"))
      (node (ref "C28") (pin "2") (pinfunction "2_2") (pintype "passive"))
      (node (ref "CN1") (pin "4") (pinfunction "4_4") (pintype "passive"))
      (node (ref "CN2") (pin "4") (pinfunction "4_4") (pintype "passive"))
      (node (ref "CN3") (pin "4") (pinfunction "4_4") (pintype "passive"))
      (node (ref "CN4") (pin "4") (pinfunction "4_4") (pintype "passive"))
      (node (ref "CN5") (pin "4") (pinfunction "4_4") (pintype "passive"))
      (node (ref "CN6") (pin "4") (pinfunction "4_4") (pintype "passive"))
      (node (ref "D4") (pin "2") (pinfunction "2_2") (pintype "passive"))
      (node (ref "L2") (pin "2") (pinfunction "2_2") (pintype "passive"))
      (node (ref "R11") (pin "2") (pinfunction "2_2") (pintype "passive"))
      (node (ref "R17") (pin "1") (pinfunction "1_1") (pintype "passive"))
      (node (ref "R5") (pin "1") (pinfunction "1_1") (pintype "passive"))
      (node (ref "U2") (pin "1") (pinfunction "IN_1") (pintype "passive"))
      (node (ref "U4") (pin "3") (pinfunction "VCC_3") (pintype "passive"))
    )
    (net (code "29") (name "24V") (class "Default")
      (node (ref "C19") (pin "1") (pinfunction "1_1") (pintype "passive"))
      (node (ref "C20") (pin "1") (pinfunction "1_1") (pintype "passive"))
      (node (ref "C23") (pin "1") (pinfunction "1_1") (pintype "passive"))
      (node (ref "C24") (pin "1") (pinfunction "1_1") (pintype "passive"))
      (node (ref "C25") (pin "1") (pinfunction "1_1") (pintype "passive"))
      (node (ref "C26") (pin "1") (pinfunction "1_1") (pintype "passive"))
      (node (ref "C27") (pin "1") (pinfunction "1_1") (pintype "passive"))
      (node (ref "Q1") (pin "2") (pinfunction "S_2") (pintype "passive"))
      (node (ref "R13") (pin "2") (pinfunction "2_2") (pintype "passive"))
      (node (ref "R14") (pin "1") (pinfunction "1_1") (pintype "passive"))
      (node (ref "R4") (pin "1") (pinfunction "1_1") (pintype "passive"))
      (node (ref "U3") (pin "5") (pinfunction "IN_5") (pintype "passive"))
    )
    (net (code "30") (name "24V_IN") (class "Default")
      (node (ref "P1") (pin "1") (pinfunction "PAD_VCC_1") (pintype "passive"))
      (node (ref "S2") (pin "1") (pinfunction "1_1") (pintype "passive"))
    )
    (net (code "31") (name "GND") (class "Default")
      (node (ref "C1") (pin "1") (pinfunction "1_1") (pintype "passive"))
      (node (ref "C10") (pin "2") (pinfunction "2_2") (pintype "passive"))
      (node (ref "C11") (pin "2") (pinfunction "2_2") (pintype "passive"))
      (node (ref "C12") (pin "2") (pinfunction "2_2") (pintype "passive"))
      (node (ref "C13") (pin "2") (pinfunction "2_2") (pintype "passive"))
      (node (ref "C14") (pin "2") (pinfunction "2_2") (pintype "passive"))
      (node (ref "C15") (pin "2") (pinfunction "2_2") (pintype "passive"))
      (node (ref "C16") (pin "2") (pinfunction "2_2") (pintype "passive"))
      (node (ref "C18") (pin "2") (pinfunction "2_2") (pintype "passive"))
      (node (ref "C19") (pin "2") (pinfunction "2_2") (pintype "passive"))
      (node (ref "C2") (pin "1") (pinfunction "1_1") (pintype "passive"))
      (node (ref "C20") (pin "2") (pinfunction "2_2") (pintype "passive"))
      (node (ref "C21") (pin "2") (pinfunction "2_2") (pintype "passive"))
      (node (ref "C22") (pin "2") (pinfunction "2_2") (pintype "passive"))
      (node (ref "C23") (pin "2") (pinfunction "2_2") (pintype "passive"))
      (node (ref "C24") (pin "2") (pinfunction "2_2") (pintype "passive"))
      (node (ref "C25") (pin "2") (pinfunction "2_2") (pintype "passive"))
      (node (ref "C26") (pin "2") (pinfunction "2_2") (pintype "passive"))
      (node (ref "C27") (pin "2") (pinfunction "2_2") (pintype "passive"))
      (node (ref "C28") (pin "1") (pinfunction "1_1") (pintype "passive"))
      (node (ref "C29") (pin "1") (pinfunction "1_1") (pintype "passive"))
      (node (ref "C3") (pin "1") (pinfunction "1_1") (pintype "passive"))
      (node (ref "C30") (pin "2") (pinfunction "2_2") (pintype "passive"))
      (node (ref "C31") (pin "2") (pinfunction "2_2") (pintype "passive"))
      (node (ref "C4") (pin "1") (pinfunction "1_1") (pintype "passive"))
      (node (ref "C5") (pin "2") (pinfunction "2_2") (pintype "passive"))
      (node (ref "C6") (pin "2") (pinfunction "2_2") (pintype "passive"))
      (node (ref "C7") (pin "2") (pinfunction "2_2") (pintype "passive"))
      (node (ref "C8") (pin "2") (pinfunction "2_2") (pintype "passive"))
      (node (ref "C9") (pin "2") (pinfunction "2_2") (pintype "passive"))
      (node (ref "CN1") (pin "3") (pinfunction "3_3") (pintype "passive"))
      (node (ref "CN1") (pin "5") (pinfunction "5_5") (pintype "passive"))
      (node (ref "CN1") (pin "6") (pinfunction "6_6") (pintype "passive"))
      (node (ref "CN2") (pin "3") (pinfunction "3_3") (pintype "passive"))
      (node (ref "CN2") (pin "5") (pinfunction "5_5") (pintype "passive"))
      (node (ref "CN2") (pin "6") (pinfunction "6_6") (pintype "passive"))
      (node (ref "CN3") (pin "3") (pinfunction "3_3") (pintype "passive"))
      (node (ref "CN3") (pin "5") (pinfunction "5_5") (pintype "passive"))
      (node (ref "CN3") (pin "6") (pinfunction "6_6") (pintype "passive"))
      (node (ref "CN4") (pin "3") (pinfunction "3_3") (pintype "passive"))
      (node (ref "CN4") (pin "5") (pinfunction "5_5") (pintype "passive"))
      (node (ref "CN4") (pin "6") (pinfunction "6_6") (pintype "passive"))
      (node (ref "CN5") (pin "3") (pinfunction "3_3") (pintype "passive"))
      (node (ref "CN5") (pin "5") (pinfunction "5_5") (pintype "passive"))
      (node (ref "CN5") (pin "6") (pinfunction "6_6") (pintype "passive"))
      (node (ref "CN6") (pin "3") (pinfunction "3_3") (pintype "passive"))
      (node (ref "CN6") (pin "5") (pinfunction "5_5") (pintype "passive"))
      (node (ref "CN6") (pin "6") (pinfunction "6_6") (pintype "passive"))
      (node (ref "CN7") (pin "3") (pinfunction "3_3") (pintype "passive"))
      (node (ref "CN7") (pin "4") (pinfunction "4_4") (pintype "passive"))
      (node (ref "D1") (pin "2") (pinfunction "2_2") (pintype "passive"))
      (node (ref "D10") (pin "1") (pinfunction "A_1") (pintype "passive"))
      (node (ref "D11") (pin "1") (pinfunction "A_1") (pintype "passive"))
      (node (ref "D12") (pin "1") (pinfunction "A_1") (pintype "passive"))
      (node (ref "D13") (pin "1") (pinfunction "A_1") (pintype "passive"))
      (node (ref "D14") (pin "2") (pinfunction "2_2") (pintype "passive"))
      (node (ref "D15") (pin "2") (pinfunction "2_2") (pintype "passive"))
      (node (ref "D16") (pin "2") (pinfunction "2_2") (pintype "passive"))
      (node (ref "D19") (pin "1") (pinfunction "A_1") (pintype "passive"))
      (node (ref "D2") (pin "2") (pinfunction "2_2") (pintype "passive"))
      (node (ref "D20") (pin "1") (pinfunction "A_1") (pintype "passive"))
      (node (ref "D21") (pin "1") (pinfunction "A_1") (pintype "passive"))
      (node (ref "D22") (pin "1") (pinfunction "A_1") (pintype "passive"))
      (node (ref "D23") (pin "1") (pinfunction "A_1") (pintype "passive"))
      (node (ref "D24") (pin "1") (pinfunction "A_1") (pintype "passive"))
      (node (ref "D25") (pin "1") (pinfunction "A_1") (pintype "passive"))
      (node (ref "D26") (pin "1") (pinfunction "A_1") (pintype "passive"))
      (node (ref "D3") (pin "2") (pinfunction "2_2") (pintype "passive"))
      (node (ref "D8") (pin "1") (pinfunction "A_1") (pintype "passive"))
      (node (ref "D9") (pin "1") (pinfunction "A_1") (pintype "passive"))
      (node (ref "P2") (pin "1") (pinfunction "PAD_VCC_1") (pintype "passive"))
      (node (ref "R10") (pin "1") (pinfunction "1_1") (pintype "passive"))
      (node (ref "R12") (pin "1") (pinfunction "1_1") (pintype "passive"))
      (node (ref "R15") (pin "2") (pinfunction "2_2") (pintype "passive"))
      (node (ref "R16") (pin "2") (pinfunction "2_2") (pintype "passive"))
      (node (ref "R32") (pin "2") (pinfunction "2_2") (pintype "passive"))
      (node (ref "R8") (pin "1") (pinfunction "1_1") (pintype "passive"))
      (node (ref "R9") (pin "1") (pinfunction "1_1") (pintype "passive"))
      (node (ref "S1") (pin "3") (pinfunction "3_3") (pintype "passive"))
      (node (ref "S1") (pin "4") (pinfunction "4_4") (pintype "passive"))
      (node (ref "U1") (pin "12") (pinfunction "VSSA_12") (pintype "passive"))
      (node (ref "U1") (pin "18") (pinfunction "VSS_4_18") (pintype "passive"))
      (node (ref "U1") (pin "31") (pinfunction "VSS_1_31") (pintype "passive"))
      (node (ref "U1") (pin "47") (pinfunction "VSS_2_47") (pintype "passive"))
      (node (ref "U1") (pin "63") (pinfunction "VSS_3_63") (pintype "passive"))
      (node (ref "U2") (pin "2") (pinfunction "GND_2") (pintype "passive"))
      (node (ref "U3") (pin "3") (pinfunction "GND_3") (pintype "passive"))
      (node (ref "U3") (pin "4") (pinfunction "GND_4") (pintype "passive"))
      (node (ref "U4") (pin "2") (pinfunction "GND_2") (pintype "passive"))
      (node (ref "U4") (pin "8") (pinfunction "S_8") (pintype "passive"))
      (node (ref "X1") (pin "2") (pinfunction "GND_2") (pintype "passive"))
    )
    (net (code "32") (name "Net-(D1-Pad1)") (class "Default")
      (node (ref "D1") (pin "1") (pinfunction "1_1") (pintype "passive"))
      (node (ref "R4") (pin "2") (pinfunction "2_2") (pintype "passive"))
    )
    (net (code "33") (name "Net-(D2-Pad1)") (class "Default")
      (node (ref "D2") (pin "1") (pinfunction "1_1") (pintype "passive"))
      (node (ref "R5") (pin "2") (pinfunction "2_2") (pintype "passive"))
    )
    (net (code "34") (name "Net-(D3-Pad1)") (class "Default")
      (node (ref "D3") (pin "1") (pinfunction "1_1") (pintype "passive"))
      (node (ref "R7") (pin "2") (pinfunction "2_2") (pintype "passive"))
    )
    (net (code "35") (name "Net-(D8-C)") (class "Default")
      (node (ref "CN1") (pin "1") (pinfunction "1_1") (pintype "passive"))
      (node (ref "D5") (pin "2") (pinfunction "2_2") (pintype "passive"))
      (node (ref "D8") (pin "2") (pinfunction "C_2") (pintype "passive"))
    )
    (net (code "36") (name "Net-(D9-C)") (class "Default")
      (node (ref "CN1") (pin "2") (pinfunction "2_2") (pintype "passive"))
      (node (ref "D9") (pin "2") (pinfunction "C_2") (pintype "passive"))
      (node (ref "R21") (pin "1") (pinfunction "1_1") (pintype "passive"))
    )
    (net (code "37") (name "Net-(D10-C)") (class "Default")
      (node (ref "CN2") (pin "1") (pinfunction "1_1") (pintype "passive"))
      (node (ref "D10") (pin "2") (pinfunction "C_2") (pintype "passive"))
      (node (ref "D6") (pin "2") (pinfunction "2_2") (pintype "passive"))
    )
    (net (code "38") (name "Net-(D11-C)") (class "Default")
      (node (ref "CN2") (pin "2") (pinfunction "2_2") (pintype "passive"))
      (node (ref "D11") (pin "2") (pinfunction "C_2") (pintype "passive"))
      (node (ref "R22") (pin "1") (pinfunction "1_1") (pintype "passive"))
    )
    (net (code "39") (name "Net-(D12-C)") (class "Default")
      (node (ref "CN3") (pin "1") (pinfunction "1_1") (pintype "passive"))
      (node (ref "D12") (pin "2") (pinfunction "C_2") (pintype "passive"))
      (node (ref "D7") (pin "2") (pinfunction "2_2") (pintype "passive"))
    )
    (net (code "40") (name "Net-(D13-C)") (class "Default")
      (node (ref "CN3") (pin "2") (pinfunction "2_2") (pintype "passive"))
      (node (ref "D13") (pin "2") (pinfunction "C_2") (pintype "passive"))
      (node (ref "R23") (pin "1") (pinfunction "1_1") (pintype "passive"))
    )
    (net (code "41") (name "Net-(D14-Pad1)") (class "Default")
      (node (ref "D14") (pin "1") (pinfunction "1_1") (pintype "passive"))
      (node (ref "R24") (pin "2") (pinfunction "2_2") (pintype "passive"))
    )
    (net (code "42") (name "Net-(D15-Pad1)") (class "Default")
      (node (ref "D15") (pin "1") (pinfunction "1_1") (pintype "passive"))
      (node (ref "R25") (pin "2") (pinfunction "2_2") (pintype "passive"))
    )
    (net (code "43") (name "Net-(D16-Pad1)") (class "Default")
      (node (ref "D16") (pin "1") (pinfunction "1_1") (pintype "passive"))
      (node (ref "R26") (pin "2") (pinfunction "2_2") (pintype "passive"))
    )
    (net (code "44") (name "Net-(D19-C)") (class "Default")
      (node (ref "CN4") (pin "1") (pinfunction "1_1") (pintype "passive"))
      (node (ref "D17") (pin "2") (pinfunction "2_2") (pintype "passive"))
      (node (ref "D19") (pin "2") (pinfunction "C_2") (pintype "passive"))
    )
    (net (code "45") (name "Net-(D20-C)") (class "Default")
      (node (ref "CN4") (pin "2") (pinfunction "2_2") (pintype "passive"))
      (node (ref "D20") (pin "2") (pinfunction "C_2") (pintype "passive"))
      (node (ref "R29") (pin "1") (pinfunction "1_1") (pintype "passive"))
    )
    (net (code "46") (name "Net-(D21-C)") (class "Default")
      (node (ref "CN5") (pin "1") (pinfunction "1_1") (pintype "passive"))
      (node (ref "D18") (pin "2") (pinfunction "2_2") (pintype "passive"))
      (node (ref "D21") (pin "2") (pinfunction "C_2") (pintype "passive"))
    )
    (net (code "47") (name "Net-(D22-C)") (class "Default")
      (node (ref "CN5") (pin "2") (pinfunction "2_2") (pintype "passive"))
      (node (ref "D22") (pin "2") (pinfunction "C_2") (pintype "passive"))
      (node (ref "R30") (pin "1") (pinfunction "1_1") (pintype "passive"))
    )
    (net (code "48") (name "Net-(Q1-D)") (class "Default")
      (node (ref "Q1") (pin "3") (pinfunction "D_3") (pintype "passive"))
      (node (ref "S2") (pin "2") (pinfunction "2_2") (pintype "passive"))
    )
    (net (code "49") (name "Net-(Q1-G)") (class "Default")
      (node (ref "Q1") (pin "1") (pinfunction "G_1") (pintype "passive"))
      (node (ref "R14") (pin "2") (pinfunction "2_2") (pintype "passive"))
      (node (ref "R16") (pin "1") (pinfunction "1_1") (pintype "passive"))
    )
    (net (code "50") (name "Net-(U2-EN)") (class "Default")
      (node (ref "R17") (pin "2") (pinfunction "2_2") (pintype "passive"))
      (node (ref "U2") (pin "3") (pinfunction "EN_3") (pintype "passive"))
    )
    (net (code "51") (name "Net-(U3-BS)") (class "Default")
      (node (ref "C17") (pin "2") (pinfunction "2_2") (pintype "passive"))
      (node (ref "U3") (pin "7") (pinfunction "BS_7") (pintype "passive"))
    )
    (net (code "52") (name "Net-(U3-EN)") (class "Default")
      (node (ref "R12") (pin "2") (pinfunction "2_2") (pintype "passive"))
      (node (ref "R13") (pin "1") (pinfunction "1_1") (pintype "passive"))
      (node (ref "U3") (pin "8") (pinfunction "EN_8") (pintype "passive"))
    )
    (net (code "53") (name "Net-(U3-FB)") (class "Default")
      (node (ref "R10") (pin "2") (pinfunction "2_2") (pintype "passive"))
      (node (ref "R11") (pin "1") (pinfunction "1_1") (pintype "passive"))
      (node (ref "U3") (pin "1") (pinfunction "FB_1") (pintype "passive"))
    )
    (net (code "54") (name "Net-(U3-FS)") (class "Default")
      (node (ref "R15") (pin "1") (pinfunction "1_1") (pintype "passive"))
      (node (ref "U3") (pin "2") (pinfunction "FS_2") (pintype "passive"))
    )
    (net (code "55") (name "Net-(U3-LX)") (class "Default")
      (node (ref "C17") (pin "1") (pinfunction "1_1") (pintype "passive"))
      (node (ref "L2") (pin "1") (pinfunction "1_1") (pintype "passive"))
      (node (ref "U3") (pin "6") (pinfunction "LX_6") (pintype "passive"))
    )
    (net (code "56") (name "Net-(X1-OE{slash}#ST{slash}NC)") (class "Default")
      (node (ref "R1") (pin "1") (pinfunction "1_1") (pintype "passive"))
      (node (ref "X1") (pin "1") (pinfunction "OE/#ST/NC_1") (pintype "passive"))
    )
    (net (code "57") (name "Net-(X1-OUT)") (class "Default")
      (node (ref "R3") (pin "1") (pinfunction "1_1") (pintype "passive"))
      (node (ref "X1") (pin "3") (pinfunction "OUT_3") (pintype "passive"))
    )
    (net (code "58") (name "Net-(X1-VDD)") (class "Default")
      (node (ref "C2") (pin "2") (pinfunction "2_2") (pintype "passive"))
      (node (ref "L1") (pin "1") (pinfunction "1_1") (pintype "passive"))
      (node (ref "R1") (pin "2") (pinfunction "2_2") (pintype "passive"))
      (node (ref "X1") (pin "4") (pinfunction "VDD_4") (pintype "passive"))
    )
    (net (code "59") (name "unconnected-(U1-PA0-WKUP-Pad14)") (class "Default")
      (node (ref "U1") (pin "14") (pinfunction "PA0-WKUP_14") (pintype "passive"))
    )
    (net (code "60") (name "unconnected-(U1-PA1-Pad15)") (class "Default")
      (node (ref "U1") (pin "15") (pinfunction "PA1_15") (pintype "passive"))
    )
    (net (code "61") (name "unconnected-(U1-PA4-Pad20)") (class "Default")
      (node (ref "U1") (pin "20") (pinfunction "PA4_20") (pintype "passive"))
    )
    (net (code "62") (name "unconnected-(U1-PA5-Pad21)") (class "Default")
      (node (ref "U1") (pin "21") (pinfunction "PA5_21") (pintype "passive"))
    )
    (net (code "63") (name "unconnected-(U1-PA6-Pad22)") (class "Default")
      (node (ref "U1") (pin "22") (pinfunction "PA6_22") (pintype "passive"))
    )
    (net (code "64") (name "unconnected-(U1-PA7-Pad23)") (class "Default")
      (node (ref "U1") (pin "23") (pinfunction "PA7_23") (pintype "passive"))
    )
    (net (code "65") (name "unconnected-(U1-PA8-Pad41)") (class "Default")
      (node (ref "U1") (pin "41") (pinfunction "PA8_41") (pintype "passive"))
    )
    (net (code "66") (name "unconnected-(U1-PA15-Pad50)") (class "Default")
      (node (ref "U1") (pin "50") (pinfunction "PA15_50") (pintype "passive"))
    )
    (net (code "67") (name "unconnected-(U1-PB0-Pad26)") (class "Default")
      (node (ref "U1") (pin "26") (pinfunction "PB0_26") (pintype "passive"))
    )
    (net (code "68") (name "unconnected-(U1-PB1-Pad27)") (class "Default")
      (node (ref "U1") (pin "27") (pinfunction "PB1_27") (pintype "passive"))
    )
    (net (code "69") (name "unconnected-(U1-PB3-Pad55)") (class "Default")
      (node (ref "U1") (pin "55") (pinfunction "PB3_55") (pintype "passive"))
    )
    (net (code "70") (name "unconnected-(U1-PB4-Pad56)") (class "Default")
      (node (ref "U1") (pin "56") (pinfunction "PB4_56") (pintype "passive"))
    )
    (net (code "71") (name "unconnected-(U1-PB5-Pad57)") (class "Default")
      (node (ref "U1") (pin "57") (pinfunction "PB5_57") (pintype "passive"))
    )
    (net (code "72") (name "unconnected-(U1-PB6-Pad58)") (class "Default")
      (node (ref "U1") (pin "58") (pinfunction "PB6_58") (pintype "passive"))
    )
    (net (code "73") (name "unconnected-(U1-PB7-Pad59)") (class "Default")
      (node (ref "U1") (pin "59") (pinfunction "PB7_59") (pintype "passive"))
    )
    (net (code "74") (name "unconnected-(U1-PB8-Pad61)") (class "Default")
      (node (ref "U1") (pin "61") (pinfunction "PB8_61") (pintype "passive"))
    )
    (net (code "75") (name "unconnected-(U1-PB9-Pad62)") (class "Default")
      (node (ref "U1") (pin "62") (pinfunction "PB9_62") (pintype "passive"))
    )
    (net (code "76") (name "unconnected-(U1-PB15-Pad36)") (class "Default")
      (node (ref "U1") (pin "36") (pinfunction "PB15_36") (pintype "passive"))
    )
    (net (code "77") (name "unconnected-(U1-PC0-Pad8)") (class "Default")
      (node (ref "U1") (pin "8") (pinfunction "PC0_8") (pintype "passive"))
    )
    (net (code "78") (name "unconnected-(U1-PC1-Pad9)") (class "Default")
      (node (ref "U1") (pin "9") (pinfunction "PC1_9") (pintype "passive"))
    )
    (net (code "79") (name "unconnected-(U1-PC2-Pad10)") (class "Default")
      (node (ref "U1") (pin "10") (pinfunction "PC2_10") (pintype "passive"))
    )
    (net (code "80") (name "unconnected-(U1-PC3-Pad11)") (class "Default")
      (node (ref "U1") (pin "11") (pinfunction "PC3_11") (pintype "passive"))
    )
    (net (code "81") (name "unconnected-(U1-PC4-Pad24)") (class "Default")
      (node (ref "U1") (pin "24") (pinfunction "PC4_24") (pintype "passive"))
    )
    (net (code "82") (name "unconnected-(U1-PC5-Pad25)") (class "Default")
      (node (ref "U1") (pin "25") (pinfunction "PC5_25") (pintype "passive"))
    )
    (net (code "83") (name "unconnected-(U1-PC6-Pad37)") (class "Default")
      (node (ref "U1") (pin "37") (pinfunction "PC6_37") (pintype "passive"))
    )
    (net (code "84") (name "unconnected-(U1-PC13-TAMPER-RTC-Pad2)") (class "Default")
      (node (ref "U1") (pin "2") (pinfunction "PC13-TAMPER-RTC_2") (pintype "passive"))
    )
    (net (code "85") (name "unconnected-(U1-PC14-OSC32_IN-Pad3)") (class "Default")
      (node (ref "U1") (pin "3") (pinfunction "PC14-OSC32_IN_3") (pintype "passive"))
    )
    (net (code "86") (name "unconnected-(U1-PC15-OSC32_OUT-Pad4)") (class "Default")
      (node (ref "U1") (pin "4") (pinfunction "PC15-OSC32_OUT_4") (pintype "passive"))
    )
    (net (code "87") (name "unconnected-(U1-PD1-OSC_OUT-Pad6)") (class "Default")
      (node (ref "U1") (pin "6") (pinfunction "PD1-OSC_OUT_6") (pintype "passive"))
    )
    (net (code "88") (name "unconnected-(U2-NC-Pad4)") (class "Default")
      (node (ref "U2") (pin "4") (pinfunction "NC_4") (pintype "passive+no_connect"))
    )
  )
)
